# NanoPi_NEO_Adapter_V1_0.net
KiCad netlist of a schematic drawn in EAGLE
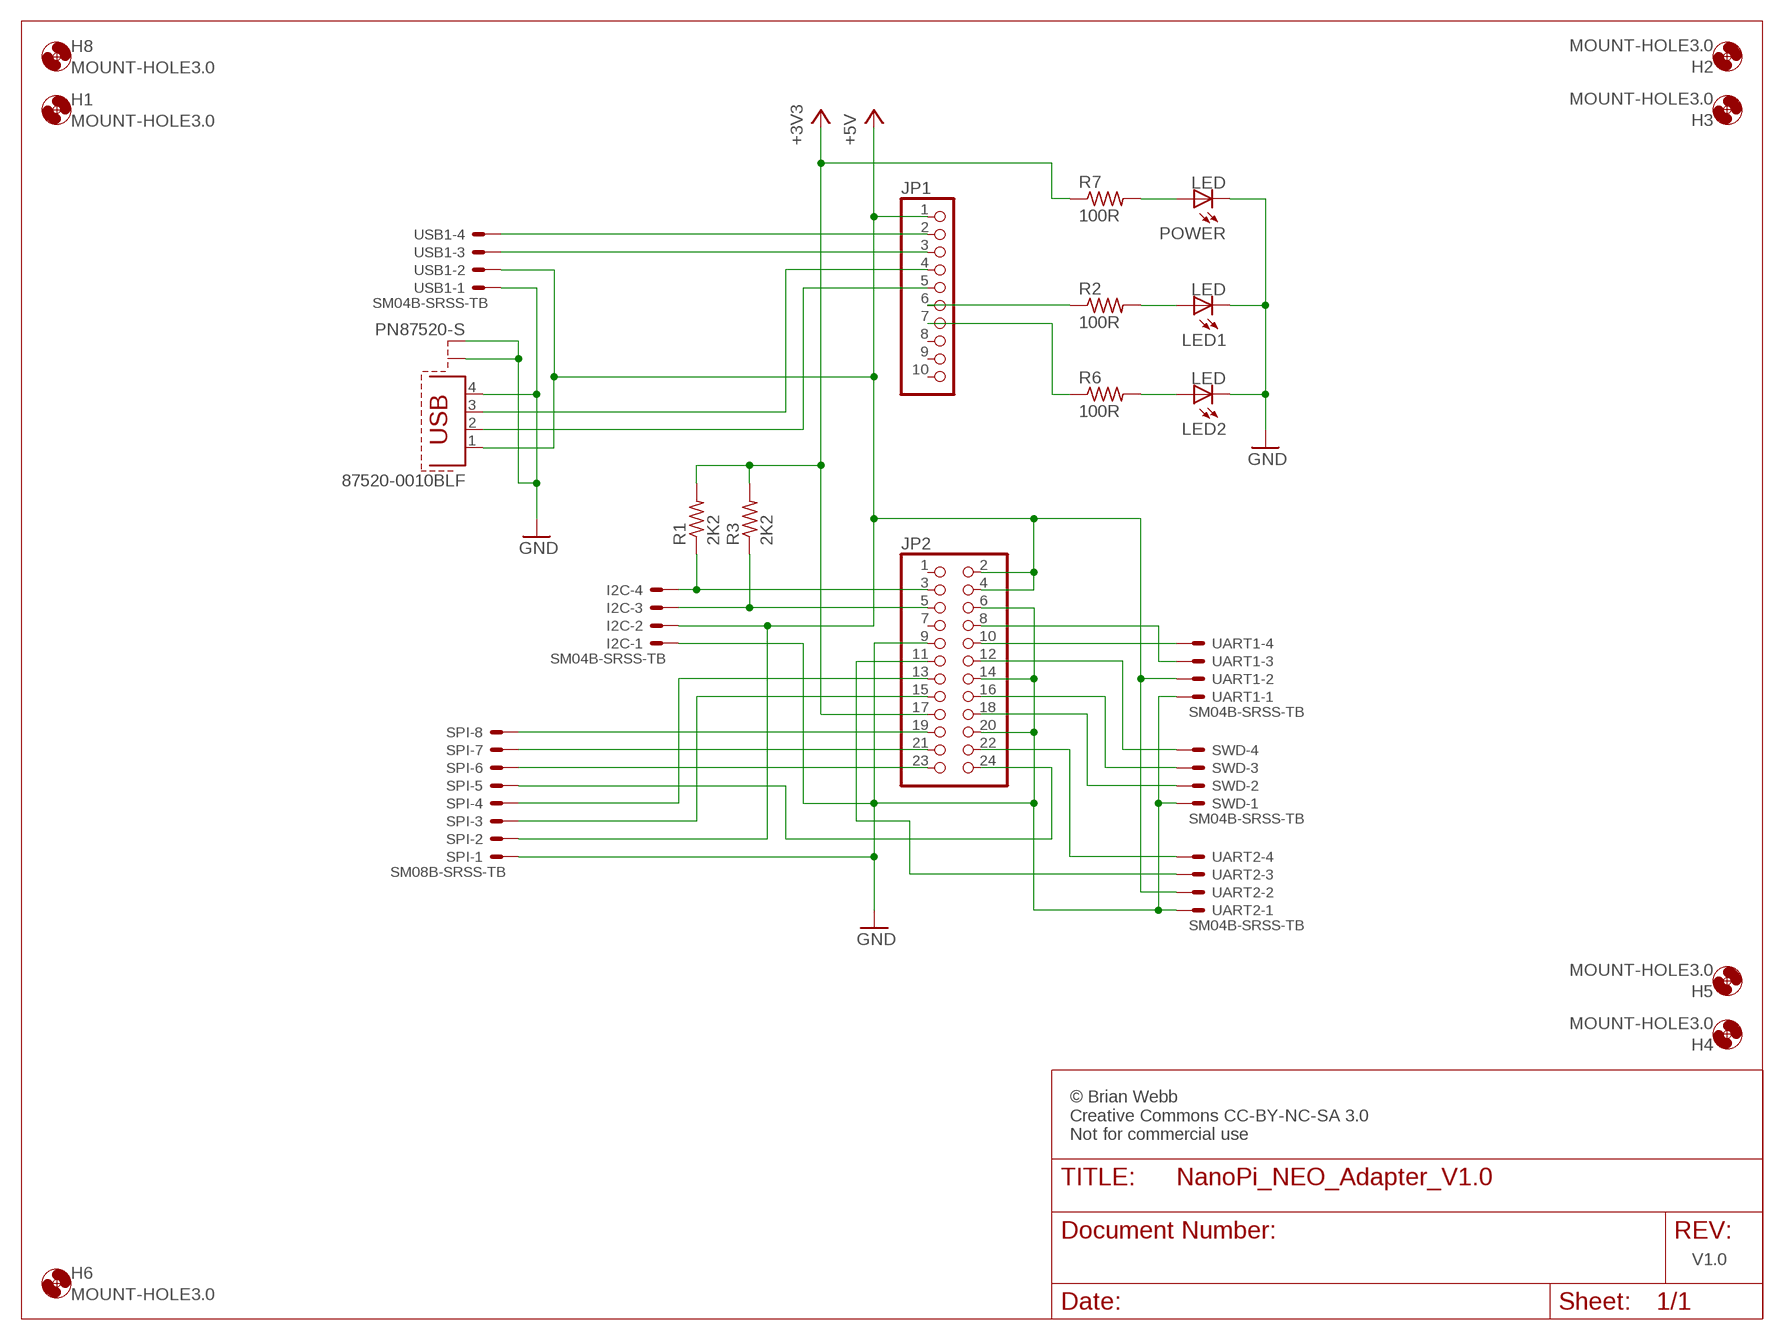
[diagram p0: schematic, sheet 1]

(export (version "E")
  (design (tool "Eeschema 10.0.6"))
  (components
    (comp (ref "87520-0010BLF")
      (value "PN87520-S")
      (footprint "eagle-import:PN87520-S")
      (libsource (lib "eagle-import") (part "PN87520-S"))
    )
    (comp (ref "H1")
      (value "MOUNT-HOLE3.0")
      (footprint "eagle-import:3,0")
      (libsource (lib "eagle-import") (part "MOUNT-HOLE3.0"))
    )
    (comp (ref "H2")
      (value "MOUNT-HOLE3.0")
      (footprint "eagle-import:3,0")
      (libsource (lib "eagle-import") (part "MOUNT-HOLE3.0"))
    )
    (comp (ref "H3")
      (value "MOUNT-HOLE3.0")
      (footprint "eagle-import:3,0")
      (libsource (lib "eagle-import") (part "MOUNT-HOLE3.0"))
    )
    (comp (ref "H4")
      (value "MOUNT-HOLE3.0")
      (footprint "eagle-import:3,0")
      (libsource (lib "eagle-import") (part "MOUNT-HOLE3.0"))
    )
    (comp (ref "H5")
      (value "MOUNT-HOLE3.0")
      (footprint "eagle-import:3,0")
      (libsource (lib "eagle-import") (part "MOUNT-HOLE3.0"))
    )
    (comp (ref "H6")
      (value "MOUNT-HOLE3.0")
      (footprint "eagle-import:3,0")
      (libsource (lib "eagle-import") (part "MOUNT-HOLE3.0"))
    )
    (comp (ref "H8")
      (value "MOUNT-HOLE3.0")
      (footprint "eagle-import:3,0")
      (libsource (lib "eagle-import") (part "MOUNT-HOLE3.0"))
    )
    (comp (ref "I2C")
      (value "SM04B-SRSS-TB")
      (footprint "eagle-import:SM04B-SRSS-TB")
      (libsource (lib "eagle-import") (part "?M04B-SRSS-TBS"))
    )
    (comp (ref "JP1")
      (value "PINHD-1X10")
      (footprint "eagle-import:1X10")
      (libsource (lib "eagle-import") (part "PINHD-1X10"))
    )
    (comp (ref "JP2")
      (value "PINHD-2X12")
      (footprint "eagle-import:2X12")
      (libsource (lib "eagle-import") (part "PINHD-2X12"))
    )
    (comp (ref "LED1")
      (value "LED")
      (footprint "eagle-import:LED0402")
      (libsource (lib "eagle-import") (part "LED_0402"))
    )
    (comp (ref "LED2")
      (value "LED")
      (footprint "eagle-import:LED0402")
      (libsource (lib "eagle-import") (part "LED_0402"))
    )
    (comp (ref "POWER")
      (value "LED")
      (footprint "eagle-import:LED0402")
      (libsource (lib "eagle-import") (part "LED_0402"))
    )
    (comp (ref "R1")
      (value "2K2")
      (footprint "eagle-import:R0402")
      (fields (field (name "PARTNO") "ERJ-2GEJ222X"))
      (libsource (lib "eagle-import") (part "R-US_R0402"))
    )
    (comp (ref "R2")
      (value "100R")
      (footprint "eagle-import:R0402")
      (fields (field (name "PARTNO") "ERJ-2GEJ222X"))
      (libsource (lib "eagle-import") (part "R-US_R0402"))
    )
    (comp (ref "R3")
      (value "2K2")
      (footprint "eagle-import:R0402")
      (fields (field (name "PARTNO") "ERJ-2GEJ222X"))
      (libsource (lib "eagle-import") (part "R-US_R0402"))
    )
    (comp (ref "R6")
      (value "100R")
      (footprint "eagle-import:R0402")
      (fields (field (name "PARTNO") "ERJ-2GEJ222X"))
      (libsource (lib "eagle-import") (part "R-US_R0402"))
    )
    (comp (ref "R7")
      (value "100R")
      (footprint "eagle-import:R0402")
      (fields (field (name "PARTNO") "ERJ-2GEJ222X"))
      (libsource (lib "eagle-import") (part "R-US_R0402"))
    )
    (comp (ref "SPI")
      (value "SM08B-SRSS-TB")
      (footprint "eagle-import:SM08B-SRSS-TB")
      (libsource (lib "eagle-import") (part "?M08B-SRSS-TBS"))
    )
    (comp (ref "SWD")
      (value "SM04B-SRSS-TB")
      (footprint "eagle-import:SM04B-SRSS-TB")
      (libsource (lib "eagle-import") (part "?M04B-SRSS-TBS"))
    )
    (comp (ref "UART1")
      (value "SM04B-SRSS-TB")
      (footprint "eagle-import:SM04B-SRSS-TB")
      (libsource (lib "eagle-import") (part "?M04B-SRSS-TBS"))
    )
    (comp (ref "UART2")
      (value "SM04B-SRSS-TB")
      (footprint "eagle-import:SM04B-SRSS-TB")
      (libsource (lib "eagle-import") (part "?M04B-SRSS-TBS"))
    )
    (comp (ref "USB1")
      (value "SM04B-SRSS-TB")
      (footprint "eagle-import:SM04B-SRSS-TB")
      (libsource (lib "eagle-import") (part "?M04B-SRSS-TBS"))
    )
  )
  (nets
    (net (code "1") (name "+3V3") (class "Default")
      (node (ref "JP2") (pin "17") (pinfunction "17_17") (pintype "passive"))
      (node (ref "R1") (pin "2") (pinfunction "2_2") (pintype "passive"))
      (node (ref "R3") (pin "2") (pinfunction "2_2") (pintype "passive"))
      (node (ref "R7") (pin "1") (pinfunction "1_1") (pintype "passive"))
    )
    (net (code "2") (name "+5V") (class "Default")
      (node (ref "87520-0010BLF") (pin "1") (pinfunction "1_1") (pintype "passive"))
      (node (ref "I2C") (pin "2") (pinfunction "S_2") (pintype "passive"))
      (node (ref "JP1") (pin "1") (pinfunction "1_1") (pintype "passive"))
      (node (ref "JP2") (pin "2") (pinfunction "2_2") (pintype "passive"))
      (node (ref "JP2") (pin "4") (pinfunction "4_4") (pintype "passive"))
      (node (ref "SPI") (pin "2") (pinfunction "S_2") (pintype "passive"))
      (node (ref "UART1") (pin "2") (pinfunction "S_2") (pintype "passive"))
      (node (ref "UART2") (pin "2") (pinfunction "S_2") (pintype "passive"))
      (node (ref "USB1") (pin "2") (pinfunction "S_2") (pintype "passive"))
    )
    (net (code "3") (name "GND") (class "Default")
      (node (ref "87520-0010BLF") (pin "4") (pinfunction "4_4") (pintype "passive"))
      (node (ref "87520-0010BLF") (pin "S1") (pinfunction "S1_S1") (pintype "passive"))
      (node (ref "87520-0010BLF") (pin "S2") (pinfunction "S2_S2") (pintype "passive"))
      (node (ref "I2C") (pin "1") (pinfunction "S_1") (pintype "passive"))
      (node (ref "JP2") (pin "14") (pinfunction "14_14") (pintype "passive"))
      (node (ref "JP2") (pin "20") (pinfunction "20_20") (pintype "passive"))
      (node (ref "JP2") (pin "6") (pinfunction "6_6") (pintype "passive"))
      (node (ref "JP2") (pin "9") (pinfunction "9_9") (pintype "passive"))
      (node (ref "LED1") (pin "C") (pinfunction "C_C") (pintype "passive"))
      (node (ref "LED2") (pin "C") (pinfunction "C_C") (pintype "passive"))
      (node (ref "POWER") (pin "C") (pinfunction "C_C") (pintype "passive"))
      (node (ref "SPI") (pin "1") (pinfunction "S_1") (pintype "passive"))
      (node (ref "SWD") (pin "1") (pinfunction "S_1") (pintype "passive"))
      (node (ref "UART1") (pin "1") (pinfunction "S_1") (pintype "passive"))
      (node (ref "UART2") (pin "1") (pinfunction "S_1") (pintype "passive"))
      (node (ref "USB1") (pin "1") (pinfunction "S_1") (pintype "passive"))
    )
    (net (code "4") (name "Net-(87520-0010BLF-Pad2)") (class "Default")
      (node (ref "87520-0010BLF") (pin "2") (pinfunction "2_2") (pintype "passive"))
      (node (ref "JP1") (pin "5") (pinfunction "5_5") (pintype "passive"))
    )
    (net (code "5") (name "Net-(87520-0010BLF-Pad3)") (class "Default")
      (node (ref "87520-0010BLF") (pin "3") (pinfunction "3_3") (pintype "passive"))
      (node (ref "JP1") (pin "4") (pinfunction "4_4") (pintype "passive"))
    )
    (net (code "6") (name "Net-(I2CC-S)") (class "Default")
      (node (ref "I2C") (pin "3") (pinfunction "S_3") (pintype "passive"))
      (node (ref "JP2") (pin "5") (pinfunction "5_5") (pintype "passive"))
      (node (ref "R3") (pin "1") (pinfunction "1_1") (pintype "passive"))
    )
    (net (code "7") (name "Net-(I2CD-S)") (class "Default")
      (node (ref "I2C") (pin "4") (pinfunction "S_4") (pintype "passive"))
      (node (ref "JP2") (pin "3") (pinfunction "3_3") (pintype "passive"))
      (node (ref "R1") (pin "1") (pinfunction "1_1") (pintype "passive"))
    )
    (net (code "8") (name "Net-(JP1-Pad6)") (class "Default")
      (node (ref "JP1") (pin "6") (pinfunction "6_6") (pintype "passive"))
      (node (ref "R2") (pin "1") (pinfunction "1_1") (pintype "passive"))
    )
    (net (code "9") (name "Net-(JP1-Pad7)") (class "Default")
      (node (ref "JP1") (pin "7") (pinfunction "7_7") (pintype "passive"))
      (node (ref "R6") (pin "1") (pinfunction "1_1") (pintype "passive"))
    )
    (net (code "10") (name "Net-(LED1-PadA)") (class "Default")
      (node (ref "LED1") (pin "A") (pinfunction "A_A") (pintype "passive"))
      (node (ref "R2") (pin "2") (pinfunction "2_2") (pintype "passive"))
    )
    (net (code "11") (name "Net-(LED2-PadA)") (class "Default")
      (node (ref "LED2") (pin "A") (pinfunction "A_A") (pintype "passive"))
      (node (ref "R6") (pin "2") (pinfunction "2_2") (pintype "passive"))
    )
    (net (code "12") (name "Net-(POWER-PadA)") (class "Default")
      (node (ref "POWER") (pin "A") (pinfunction "A_A") (pintype "passive"))
      (node (ref "R7") (pin "2") (pinfunction "2_2") (pintype "passive"))
    )
    (net (code "13") (name "Net-(SPIC-S)") (class "Default")
      (node (ref "JP2") (pin "15") (pinfunction "15_15") (pintype "passive"))
      (node (ref "SPI") (pin "3") (pinfunction "S_3") (pintype "passive"))
    )
    (net (code "14") (name "Net-(SPID-S)") (class "Default")
      (node (ref "JP2") (pin "13") (pinfunction "13_13") (pintype "passive"))
      (node (ref "SPI") (pin "4") (pinfunction "S_4") (pintype "passive"))
    )
    (net (code "15") (name "Net-(SPIE-S)") (class "Default")
      (node (ref "JP2") (pin "24") (pinfunction "24_24") (pintype "passive"))
      (node (ref "SPI") (pin "5") (pinfunction "S_5") (pintype "passive"))
    )
    (net (code "16") (name "Net-(SPIF-S)") (class "Default")
      (node (ref "JP2") (pin "23") (pinfunction "23_23") (pintype "passive"))
      (node (ref "SPI") (pin "6") (pinfunction "S_6") (pintype "passive"))
    )
    (net (code "17") (name "Net-(SPIG-S)") (class "Default")
      (node (ref "JP2") (pin "21") (pinfunction "21_21") (pintype "passive"))
      (node (ref "SPI") (pin "7") (pinfunction "S_7") (pintype "passive"))
    )
    (net (code "18") (name "Net-(SPIH-S)") (class "Default")
      (node (ref "JP2") (pin "19") (pinfunction "19_19") (pintype "passive"))
      (node (ref "SPI") (pin "8") (pinfunction "S_8") (pintype "passive"))
    )
    (net (code "19") (name "Net-(SWDB-S)") (class "Default")
      (node (ref "JP2") (pin "18") (pinfunction "18_18") (pintype "passive"))
      (node (ref "SWD") (pin "2") (pinfunction "S_2") (pintype "passive"))
    )
    (net (code "20") (name "Net-(SWDC-S)") (class "Default")
      (node (ref "JP2") (pin "16") (pinfunction "16_16") (pintype "passive"))
      (node (ref "SWD") (pin "3") (pinfunction "S_3") (pintype "passive"))
    )
    (net (code "21") (name "Net-(SWDD-S)") (class "Default")
      (node (ref "JP2") (pin "12") (pinfunction "12_12") (pintype "passive"))
      (node (ref "SWD") (pin "4") (pinfunction "S_4") (pintype "passive"))
    )
    (net (code "22") (name "Net-(UART1C-S)") (class "Default")
      (node (ref "JP2") (pin "8") (pinfunction "8_8") (pintype "passive"))
      (node (ref "UART1") (pin "3") (pinfunction "S_3") (pintype "passive"))
    )
    (net (code "23") (name "Net-(UART1D-S)") (class "Default")
      (node (ref "JP2") (pin "10") (pinfunction "10_10") (pintype "passive"))
      (node (ref "UART1") (pin "4") (pinfunction "S_4") (pintype "passive"))
    )
    (net (code "24") (name "Net-(UART2C-S)") (class "Default")
      (node (ref "JP2") (pin "11") (pinfunction "11_11") (pintype "passive"))
      (node (ref "UART2") (pin "3") (pinfunction "S_3") (pintype "passive"))
    )
    (net (code "25") (name "Net-(UART2D-S)") (class "Default")
      (node (ref "JP2") (pin "22") (pinfunction "22_22") (pintype "passive"))
      (node (ref "UART2") (pin "4") (pinfunction "S_4") (pintype "passive"))
    )
    (net (code "26") (name "Net-(USB1C-S)") (class "Default")
      (node (ref "JP1") (pin "3") (pinfunction "3_3") (pintype "passive"))
      (node (ref "USB1") (pin "3") (pinfunction "S_3") (pintype "passive"))
    )
    (net (code "27") (name "Net-(USB1D-S)") (class "Default")
      (node (ref "JP1") (pin "2") (pinfunction "2_2") (pintype "passive"))
      (node (ref "USB1") (pin "4") (pinfunction "S_4") (pintype "passive"))
    )
    (net (code "28") (name "unconnected-(JP1-Pad8)") (class "Default")
      (node (ref "JP1") (pin "8") (pinfunction "8_8") (pintype "passive"))
    )
    (net (code "29") (name "unconnected-(JP1-Pad9)") (class "Default")
      (node (ref "JP1") (pin "9") (pinfunction "9_9") (pintype "passive"))
    )
    (net (code "30") (name "unconnected-(JP1-Pad10)") (class "Default")
      (node (ref "JP1") (pin "10") (pinfunction "10_10") (pintype "passive"))
    )
    (net (code "31") (name "unconnected-(JP2-Pad1)") (class "Default")
      (node (ref "JP2") (pin "1") (pinfunction "1_1") (pintype "passive"))
    )
    (net (code "32") (name "unconnected-(JP2-Pad7)") (class "Default")
      (node (ref "JP2") (pin "7") (pinfunction "7_7") (pintype "passive"))
    )
  )
)
